# Photobooth-Connector.net
KiCad netlist of a schematic drawn in EAGLE
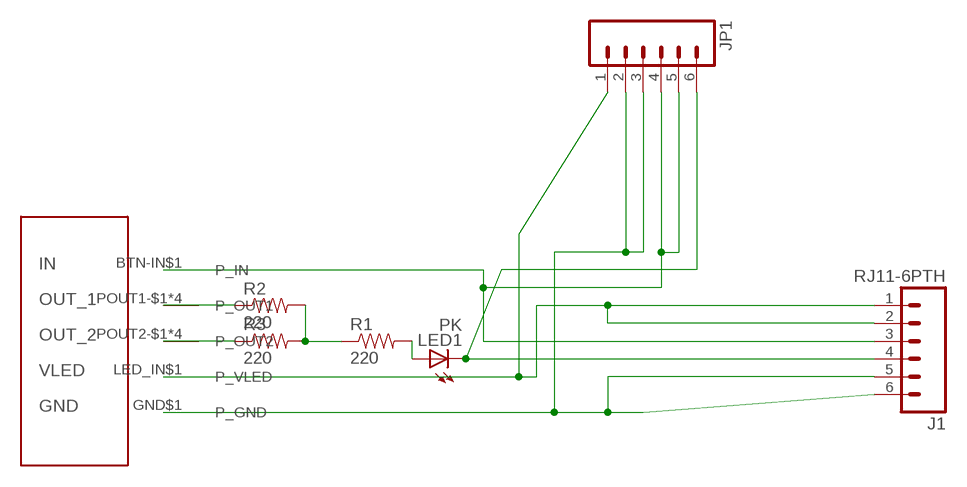
[diagram p0: schematic, sheet 1]

(export (version "E")
  (design (tool "Eeschema 10.0.6"))
  (components
    (comp (ref "J1")
      (value "RJ11-6PTH")
      (footprint "eagle-import:RJ11-6")
      (libsource (lib "eagle-import") (part "RJ11-6PTH"))
    )
    (comp (ref "JP1")
      (value "M06LOCK")
      (footprint "eagle-import:1X06_LOCK")
      (libsource (lib "eagle-import") (part "M06LOCK"))
    )
    (comp (ref "LED1")
      (value "PK")
      (footprint "eagle-import:CHIP-LED0805")
      (libsource (lib "eagle-import") (part "LEDCHIP-LED0805"))
    )
    (comp (ref "R1")
      (value "220")
      (footprint "eagle-import:0805")
      (libsource (lib "eagle-import") (part "RESISTOR0805-RES"))
    )
    (comp (ref "R2")
      (value "220")
      (footprint "eagle-import:0805")
      (libsource (lib "eagle-import") (part "RESISTOR0805-RES"))
    )
    (comp (ref "R3")
      (value "220")
      (footprint "eagle-import:0805")
      (libsource (lib "eagle-import") (part "RESISTOR0805-RES"))
    )
    (comp (ref "U$1")
      (value "KERMIS_BUTTON")
      (footprint "eagle-import:SLOT_DRILLED")
      (libsource (lib "eagle-import") (part "KERMIS_BUTTON"))
    )
  )
  (nets
    (net (code "1") (name "Net-(J1-Pad4)") (class "Default")
      (node (ref "J1") (pin "4") (pinfunction "4_4") (pintype "passive"))
      (node (ref "JP1") (pin "6") (pinfunction "6_6") (pintype "passive"))
      (node (ref "LED1") (pin "C") (pinfunction "C_C") (pintype "passive"))
    )
    (net (code "2") (name "Net-(LED1-PadA)") (class "Default")
      (node (ref "LED1") (pin "A") (pinfunction "A_A") (pintype "passive"))
      (node (ref "R1") (pin "2") (pinfunction "2_2") (pintype "passive"))
    )
    (net (code "3") (name "Net-(R1-Pad1)") (class "Default")
      (node (ref "R1") (pin "1") (pinfunction "1_1") (pintype "passive"))
      (node (ref "R2") (pin "2") (pinfunction "2_2") (pintype "passive"))
      (node (ref "R3") (pin "2") (pinfunction "2_2") (pintype "passive"))
    )
    (net (code "4") (name "Net-(R2-Pad1)") (class "Default")
      (node (ref "R2") (pin "1") (pinfunction "1_1") (pintype "passive"))
      (node (ref "U$1") (pin "POUT1-$1") (pinfunction "P_OUT1_POUT1-$1") (pintype "bidirectional"))
      (node (ref "U$1") (pin "POUT1-$2") (pinfunction "P_OUT1_POUT1-$2") (pintype "bidirectional"))
      (node (ref "U$1") (pin "POUT1-$3") (pinfunction "P_OUT1_POUT1-$3") (pintype "bidirectional"))
      (node (ref "U$1") (pin "POUT1-$4") (pinfunction "P_OUT1_POUT1-$4") (pintype "bidirectional"))
    )
    (net (code "5") (name "Net-(R3-Pad1)") (class "Default")
      (node (ref "R3") (pin "1") (pinfunction "1_1") (pintype "passive"))
      (node (ref "U$1") (pin "POUT2-$1") (pinfunction "P_OUT2_POUT2-$1") (pintype "bidirectional"))
      (node (ref "U$1") (pin "POUT2-$2") (pinfunction "P_OUT2_POUT2-$2") (pintype "bidirectional"))
      (node (ref "U$1") (pin "POUT2-$3") (pinfunction "P_OUT2_POUT2-$3") (pintype "bidirectional"))
      (node (ref "U$1") (pin "POUT2-$4") (pinfunction "P_OUT2_POUT2-$4") (pintype "bidirectional"))
    )
    (net (code "6") (name "Net-(U$1-P_GND)") (class "Default")
      (node (ref "J1") (pin "5") (pinfunction "5_5") (pintype "passive"))
      (node (ref "J1") (pin "6") (pinfunction "6_6") (pintype "passive"))
      (node (ref "JP1") (pin "2") (pinfunction "2_2") (pintype "passive"))
      (node (ref "JP1") (pin "3") (pinfunction "3_3") (pintype "passive"))
      (node (ref "U$1") (pin "GND$1") (pinfunction "P_GND_GND$1") (pintype "bidirectional"))
    )
    (net (code "7") (name "Net-(U$1-P_IN)") (class "Default")
      (node (ref "J1") (pin "3") (pinfunction "3_3") (pintype "passive"))
      (node (ref "JP1") (pin "4") (pinfunction "4_4") (pintype "passive"))
      (node (ref "JP1") (pin "5") (pinfunction "5_5") (pintype "passive"))
      (node (ref "U$1") (pin "BTN-IN$1") (pinfunction "P_IN_BTN-IN$1") (pintype "bidirectional"))
    )
    (net (code "8") (name "Net-(U$1-P_VLED)") (class "Default")
      (node (ref "J1") (pin "1") (pinfunction "1_1") (pintype "passive"))
      (node (ref "J1") (pin "2") (pinfunction "2_2") (pintype "passive"))
      (node (ref "JP1") (pin "1") (pinfunction "1_1") (pintype "passive"))
      (node (ref "U$1") (pin "LED_IN$1") (pinfunction "P_VLED_LED_IN$1") (pintype "bidirectional"))
    )
  )
)
